# 3_2.net
KiCad netlist of a schematic drawn in Altium Designer
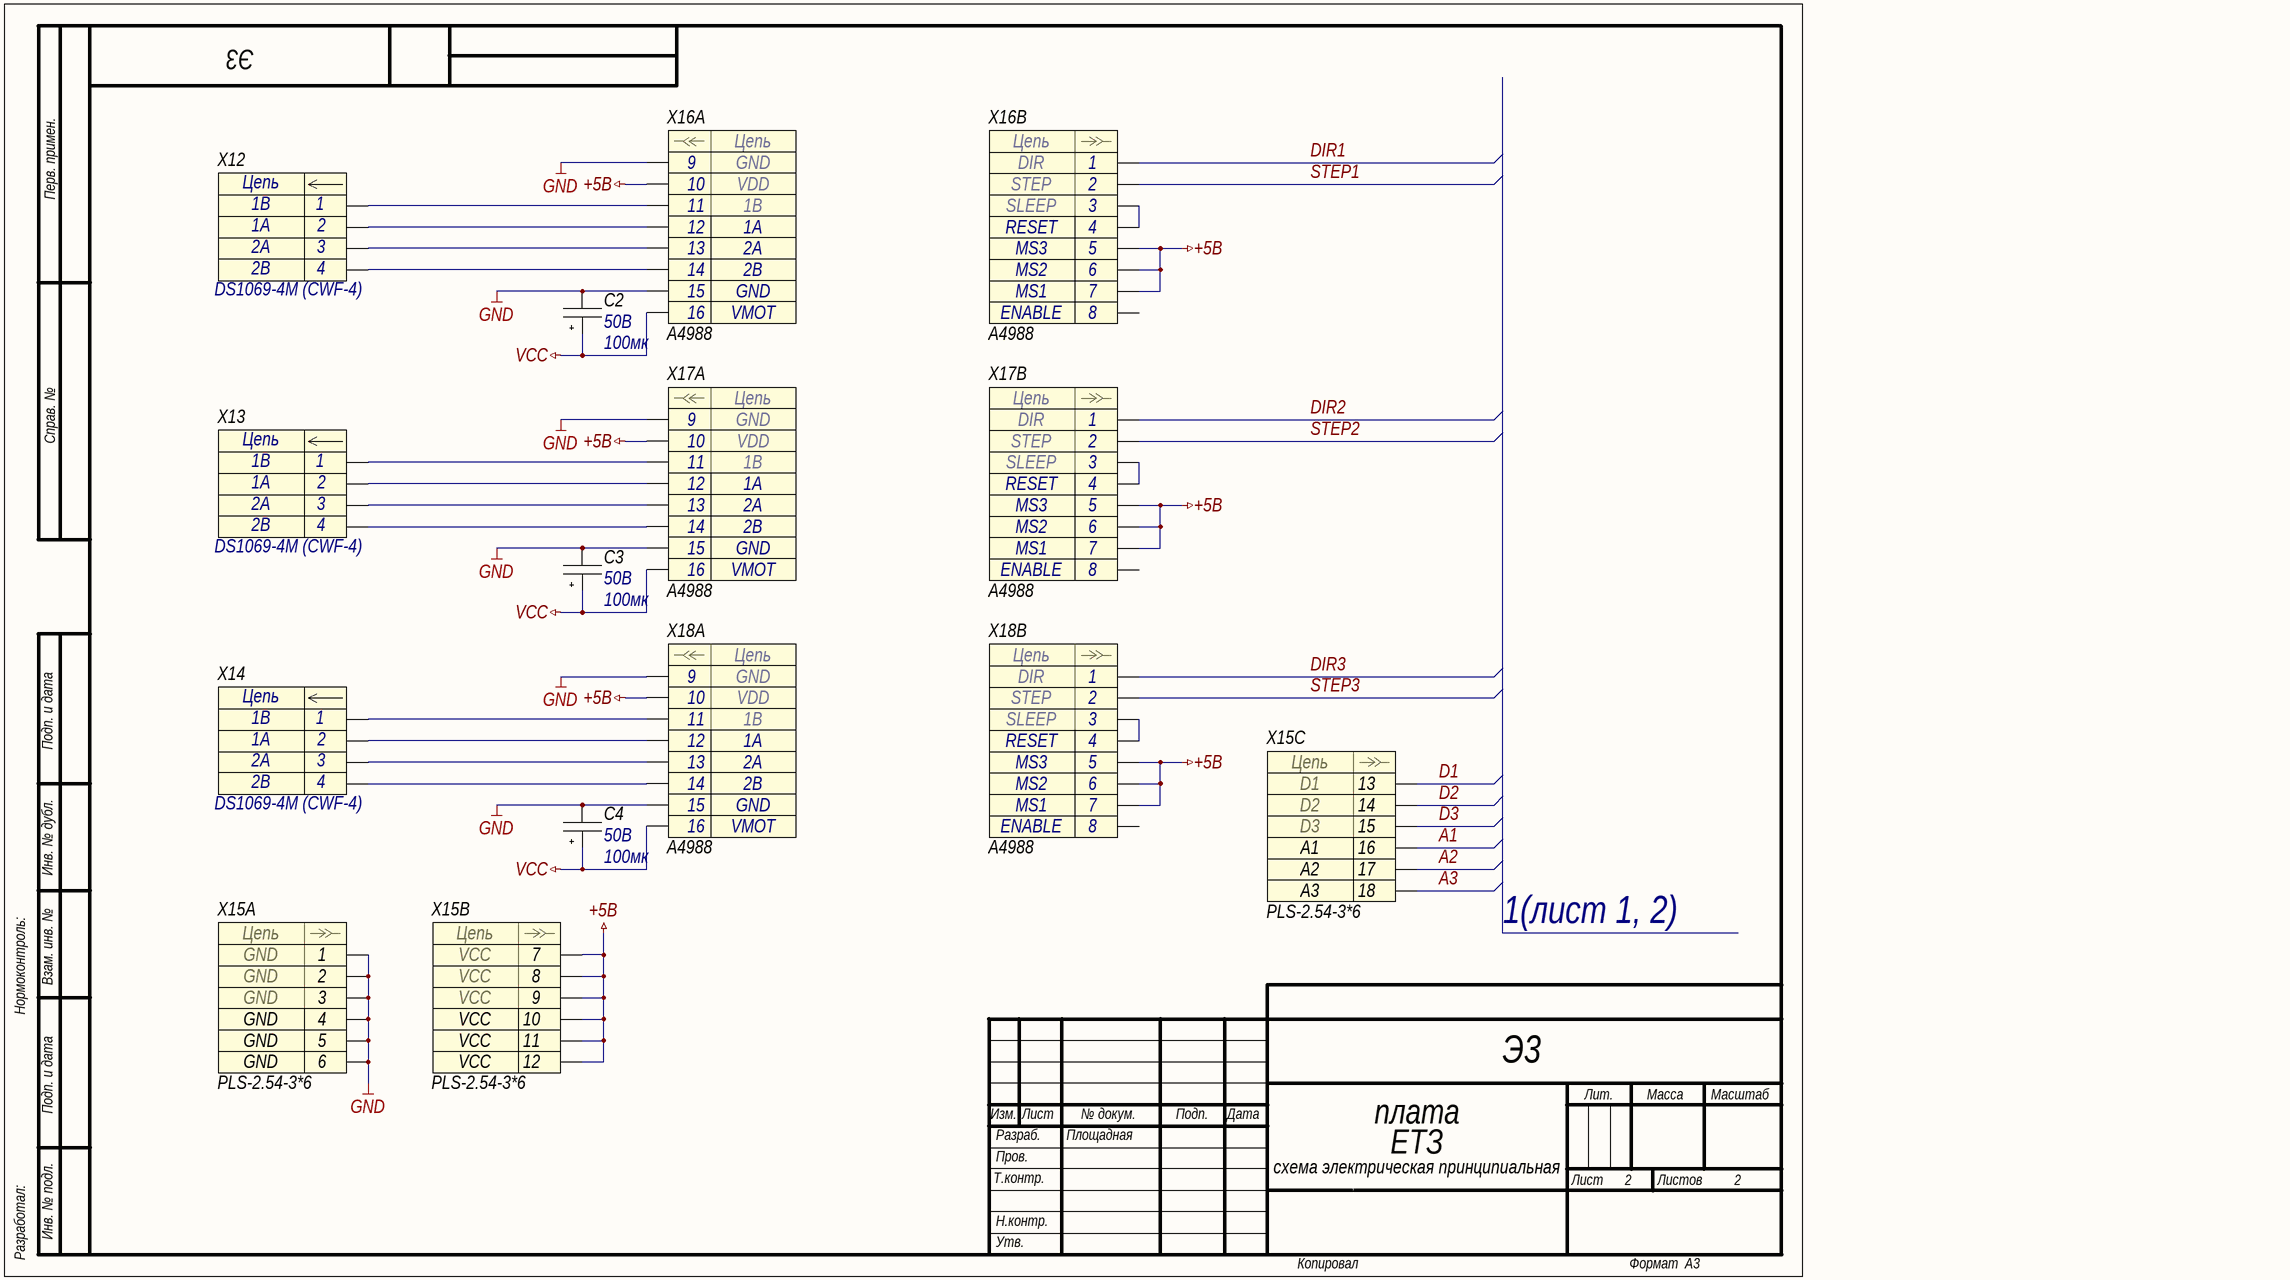
[diagram p0: Э3_2.SchDoc]

(export (version "E")
  (design (tool "Eeschema 10.0.6"))
  (components
    (comp (ref "C2")
      (value "конденсатор")
      (footprint "SK050M0100B3F-0811-up")
      (fields (field (name "VOLTAGE") "50В") (field (name "NOMINAL") "100мк"))
      (libsource (lib "LibraryPloshchadnaia") (part "SK050M0100B3F-0811"))
    )
    (comp (ref "C3")
      (value "конденсатор")
      (footprint "SK050M0100B3F-0811-up")
      (fields (field (name "VOLTAGE") "50В") (field (name "NOMINAL") "100мк"))
      (libsource (lib "LibraryPloshchadnaia") (part "SK050M0100B3F-0811"))
    )
    (comp (ref "C4")
      (value "конденсатор")
      (footprint "SK050M0100B3F-0811-up")
      (fields (field (name "VOLTAGE") "50В") (field (name "NOMINAL") "100мк"))
      (libsource (lib "LibraryPloshchadnaia") (part "SK050M0100B3F-0811"))
    )
    (comp (ref "X12")
      (value "DS1069-4M (CWF-4)")
      (footprint "CWF-4")
      (description "Разъем - 4 конт. прямая вилка на плату")
      (fields (field (name "NAME") "DS1069-4M (CWF-4)"))
      (libsource (lib "headers") (part "CWF-4"))
    )
    (comp (ref "X13")
      (value "DS1069-4M (CWF-4)")
      (footprint "CWF-4")
      (description "Разъем - 4 конт. прямая вилка на плату")
      (fields (field (name "NAME") "DS1069-4M (CWF-4)"))
      (libsource (lib "headers") (part "CWF-4"))
    )
    (comp (ref "X14")
      (value "DS1069-4M (CWF-4)")
      (footprint "CWF-4")
      (description "Разъем - 4 конт. прямая вилка на плату")
      (fields (field (name "NAME") "DS1069-4M (CWF-4)"))
      (libsource (lib "headers") (part "CWF-4"))
    )
    (comp (ref "X15")
      (value "PLS-2.54-3*6")
      (footprint "PLS-2.54-3*6")
      (libsource (lib "LibraryPloshchadnaia") (part "PLS-2.54-3*6"))
    )
    (comp (ref "X16")
      (value "A4988")
      (footprint "A4988")
      (libsource (lib "LibraryPloshchadnaia") (part "A4988"))
    )
    (comp (ref "X17")
      (value "A4988")
      (footprint "A4988")
      (libsource (lib "LibraryPloshchadnaia") (part "A4988"))
    )
    (comp (ref "X18")
      (value "A4988")
      (footprint "A4988")
      (libsource (lib "LibraryPloshchadnaia") (part "A4988"))
    )
  )
  (nets
    (net (code "1") (name "+5В") (class "Default")
      (node (ref "X15") (pin "10") (pinfunction "10_10") (pintype "passive"))
      (node (ref "X15") (pin "11") (pinfunction "11_11") (pintype "passive"))
      (node (ref "X15") (pin "12") (pinfunction "12_12") (pintype "passive"))
      (node (ref "X15") (pin "7") (pinfunction "7_7") (pintype "passive"))
      (node (ref "X15") (pin "8") (pinfunction "8_8") (pintype "passive"))
      (node (ref "X15") (pin "9") (pinfunction "9_9") (pintype "passive"))
      (node (ref "X16") (pin "10") (pinfunction "10_10") (pintype "passive"))
      (node (ref "X16") (pin "5") (pinfunction "5_5") (pintype "passive"))
      (node (ref "X16") (pin "6") (pinfunction "6_6") (pintype "passive"))
      (node (ref "X16") (pin "7") (pinfunction "7_7") (pintype "passive"))
      (node (ref "X17") (pin "10") (pinfunction "10_10") (pintype "passive"))
      (node (ref "X17") (pin "5") (pinfunction "5_5") (pintype "passive"))
      (node (ref "X17") (pin "6") (pinfunction "6_6") (pintype "passive"))
      (node (ref "X17") (pin "7") (pinfunction "7_7") (pintype "passive"))
      (node (ref "X18") (pin "10") (pinfunction "10_10") (pintype "passive"))
      (node (ref "X18") (pin "5") (pinfunction "5_5") (pintype "passive"))
      (node (ref "X18") (pin "6") (pinfunction "6_6") (pintype "passive"))
      (node (ref "X18") (pin "7") (pinfunction "7_7") (pintype "passive"))
    )
    (net (code "2") (name "/A1") (class "Default")
      (node (ref "X15") (pin "16") (pinfunction "16_16") (pintype "passive"))
    )
    (net (code "3") (name "/A2") (class "Default")
      (node (ref "X15") (pin "17") (pinfunction "17_17") (pintype "passive"))
    )
    (net (code "4") (name "/A3") (class "Default")
      (node (ref "X15") (pin "18") (pinfunction "18_18") (pintype "passive"))
    )
    (net (code "5") (name "/D1") (class "Default")
      (node (ref "X15") (pin "13") (pinfunction "13_13") (pintype "passive"))
    )
    (net (code "6") (name "/D2") (class "Default")
      (node (ref "X15") (pin "14") (pinfunction "14_14") (pintype "passive"))
    )
    (net (code "7") (name "/D3") (class "Default")
      (node (ref "X15") (pin "15") (pinfunction "15_15") (pintype "passive"))
    )
    (net (code "8") (name "/DIR1") (class "Default")
      (node (ref "X16") (pin "1") (pinfunction "1_1") (pintype "passive"))
    )
    (net (code "9") (name "/DIR2") (class "Default")
      (node (ref "X17") (pin "1") (pinfunction "1_1") (pintype "passive"))
    )
    (net (code "10") (name "/DIR3") (class "Default")
      (node (ref "X18") (pin "1") (pinfunction "1_1") (pintype "passive"))
    )
    (net (code "11") (name "/STEP1") (class "Default")
      (node (ref "X16") (pin "2") (pinfunction "2_2") (pintype "passive"))
    )
    (net (code "12") (name "/STEP2") (class "Default")
      (node (ref "X17") (pin "2") (pinfunction "2_2") (pintype "passive"))
    )
    (net (code "13") (name "/STEP3") (class "Default")
      (node (ref "X18") (pin "2") (pinfunction "2_2") (pintype "passive"))
    )
    (net (code "14") (name "GND") (class "Default")
      (node (ref "C2") (pin "2") (pinfunction "2_2") (pintype "passive"))
      (node (ref "C3") (pin "2") (pinfunction "2_2") (pintype "passive"))
      (node (ref "C4") (pin "2") (pinfunction "2_2") (pintype "passive"))
      (node (ref "X15") (pin "1") (pinfunction "1_1") (pintype "passive"))
      (node (ref "X15") (pin "2") (pinfunction "2_2") (pintype "passive"))
      (node (ref "X15") (pin "3") (pinfunction "3_3") (pintype "passive"))
      (node (ref "X15") (pin "4") (pinfunction "4_4") (pintype "passive"))
      (node (ref "X15") (pin "5") (pinfunction "5_5") (pintype "passive"))
      (node (ref "X15") (pin "6") (pinfunction "6_6") (pintype "passive"))
      (node (ref "X16") (pin "15") (pinfunction "15_15") (pintype "passive"))
      (node (ref "X16") (pin "9") (pinfunction "9_9") (pintype "passive"))
      (node (ref "X17") (pin "15") (pinfunction "15_15") (pintype "passive"))
      (node (ref "X17") (pin "9") (pinfunction "9_9") (pintype "passive"))
      (node (ref "X18") (pin "15") (pinfunction "15_15") (pintype "passive"))
      (node (ref "X18") (pin "9") (pinfunction "9_9") (pintype "passive"))
    )
    (net (code "15") (name "Net-(X12-Pad1)") (class "Default")
      (node (ref "X12") (pin "1") (pinfunction "1_1") (pintype "passive"))
      (node (ref "X16") (pin "11") (pinfunction "11_11") (pintype "passive"))
    )
    (net (code "16") (name "Net-(X12-Pad2)") (class "Default")
      (node (ref "X12") (pin "2") (pinfunction "2_2") (pintype "passive"))
      (node (ref "X16") (pin "12") (pinfunction "12_12") (pintype "passive"))
    )
    (net (code "17") (name "Net-(X12-Pad3)") (class "Default")
      (node (ref "X12") (pin "3") (pinfunction "3_3") (pintype "passive"))
      (node (ref "X16") (pin "13") (pinfunction "13_13") (pintype "passive"))
    )
    (net (code "18") (name "Net-(X12-Pad4)") (class "Default")
      (node (ref "X12") (pin "4") (pinfunction "4_4") (pintype "passive"))
      (node (ref "X16") (pin "14") (pinfunction "14_14") (pintype "passive"))
    )
    (net (code "19") (name "Net-(X13-Pad1)") (class "Default")
      (node (ref "X13") (pin "1") (pinfunction "1_1") (pintype "passive"))
      (node (ref "X17") (pin "11") (pinfunction "11_11") (pintype "passive"))
    )
    (net (code "20") (name "Net-(X13-Pad2)") (class "Default")
      (node (ref "X13") (pin "2") (pinfunction "2_2") (pintype "passive"))
      (node (ref "X17") (pin "12") (pinfunction "12_12") (pintype "passive"))
    )
    (net (code "21") (name "Net-(X13-Pad3)") (class "Default")
      (node (ref "X13") (pin "3") (pinfunction "3_3") (pintype "passive"))
      (node (ref "X17") (pin "13") (pinfunction "13_13") (pintype "passive"))
    )
    (net (code "22") (name "Net-(X13-Pad4)") (class "Default")
      (node (ref "X13") (pin "4") (pinfunction "4_4") (pintype "passive"))
      (node (ref "X17") (pin "14") (pinfunction "14_14") (pintype "passive"))
    )
    (net (code "23") (name "Net-(X14-Pad1)") (class "Default")
      (node (ref "X14") (pin "1") (pinfunction "1_1") (pintype "passive"))
      (node (ref "X18") (pin "11") (pinfunction "11_11") (pintype "passive"))
    )
    (net (code "24") (name "Net-(X14-Pad2)") (class "Default")
      (node (ref "X14") (pin "2") (pinfunction "2_2") (pintype "passive"))
      (node (ref "X18") (pin "12") (pinfunction "12_12") (pintype "passive"))
    )
    (net (code "25") (name "Net-(X14-Pad3)") (class "Default")
      (node (ref "X14") (pin "3") (pinfunction "3_3") (pintype "passive"))
      (node (ref "X18") (pin "13") (pinfunction "13_13") (pintype "passive"))
    )
    (net (code "26") (name "Net-(X14-Pad4)") (class "Default")
      (node (ref "X14") (pin "4") (pinfunction "4_4") (pintype "passive"))
      (node (ref "X18") (pin "14") (pinfunction "14_14") (pintype "passive"))
    )
    (net (code "27") (name "Net-(X16-Pad3)") (class "Default")
      (node (ref "X16") (pin "3") (pinfunction "3_3") (pintype "passive"))
      (node (ref "X16") (pin "4") (pinfunction "4_4") (pintype "passive"))
    )
    (net (code "28") (name "Net-(X17-Pad3)") (class "Default")
      (node (ref "X17") (pin "3") (pinfunction "3_3") (pintype "passive"))
      (node (ref "X17") (pin "4") (pinfunction "4_4") (pintype "passive"))
    )
    (net (code "29") (name "Net-(X18-Pad3)") (class "Default")
      (node (ref "X18") (pin "3") (pinfunction "3_3") (pintype "passive"))
      (node (ref "X18") (pin "4") (pinfunction "4_4") (pintype "passive"))
    )
    (net (code "30") (name "VCC") (class "Default")
      (node (ref "C2") (pin "1") (pinfunction "1_1") (pintype "passive"))
      (node (ref "C3") (pin "1") (pinfunction "1_1") (pintype "passive"))
      (node (ref "C4") (pin "1") (pinfunction "1_1") (pintype "passive"))
      (node (ref "X16") (pin "16") (pinfunction "16_16") (pintype "passive"))
      (node (ref "X17") (pin "16") (pinfunction "16_16") (pintype "passive"))
      (node (ref "X18") (pin "16") (pinfunction "16_16") (pintype "passive"))
    )
    (net (code "31") (name "unconnected-(X16-Pad8)") (class "Default")
      (node (ref "X16") (pin "8") (pinfunction "8_8") (pintype "passive"))
    )
    (net (code "32") (name "unconnected-(X17-Pad8)") (class "Default")
      (node (ref "X17") (pin "8") (pinfunction "8_8") (pintype "passive"))
    )
    (net (code "33") (name "unconnected-(X18-Pad8)") (class "Default")
      (node (ref "X18") (pin "8") (pinfunction "8_8") (pintype "passive"))
    )
  )
)
